# Cap_Piano_Circuit.net
KiCad netlist of a schematic drawn in EAGLE
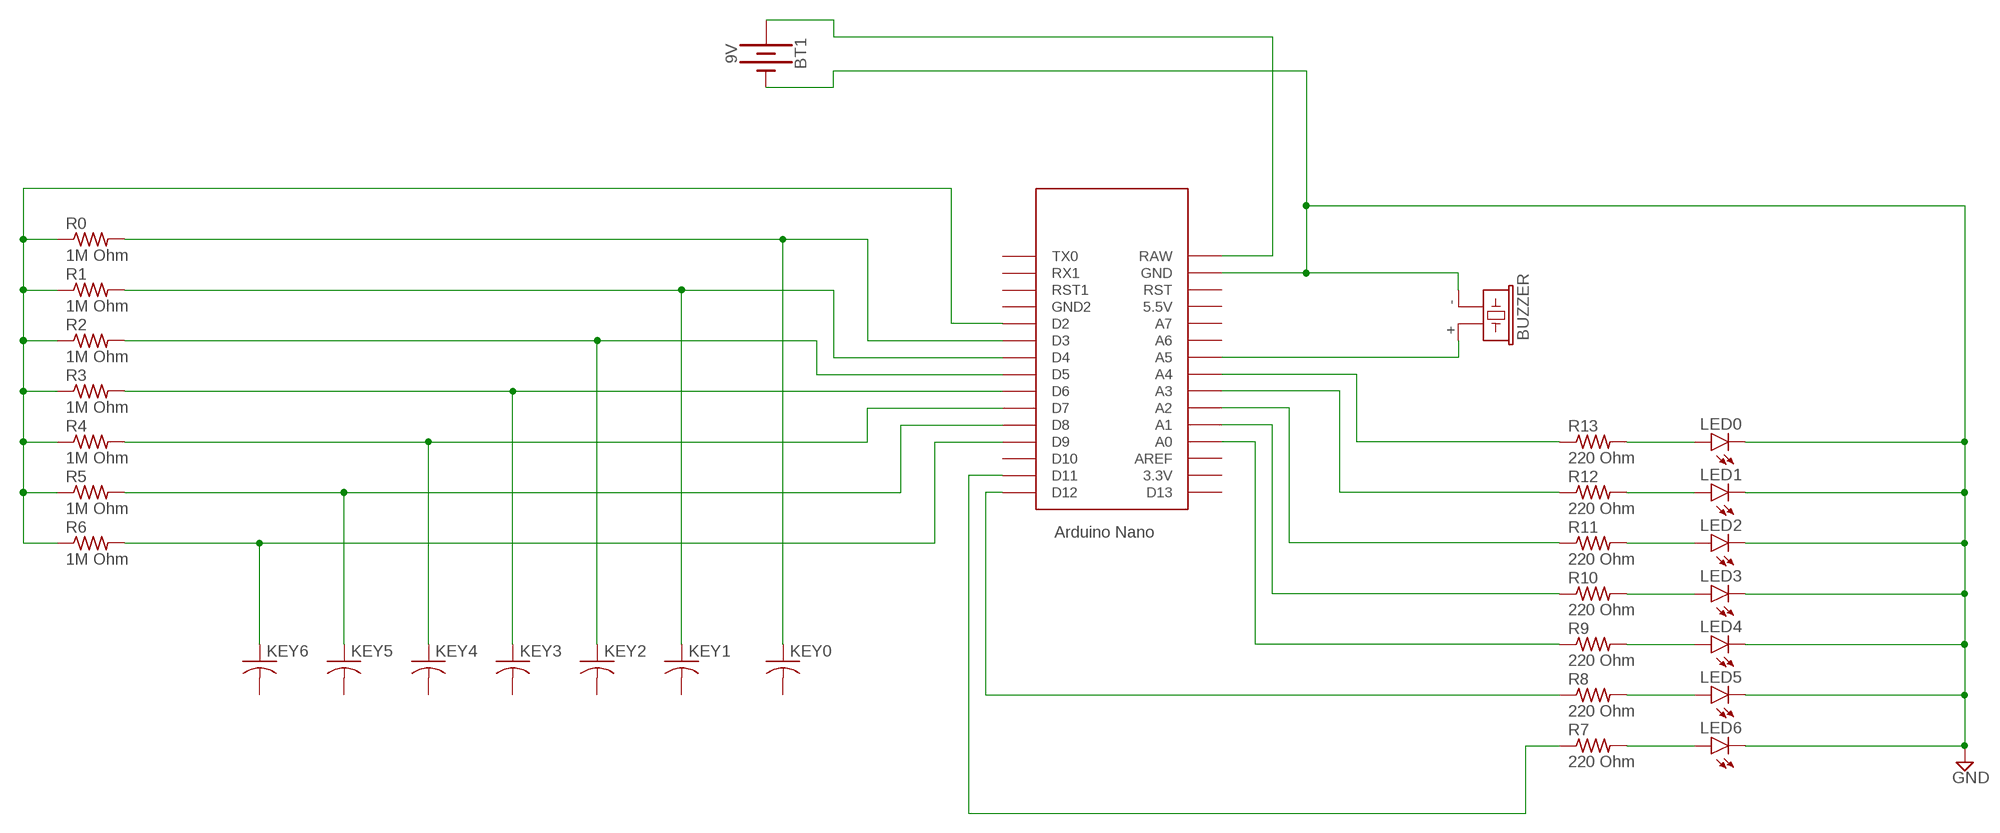
[diagram p0: schematic, sheet 1]

(export (version "E")
  (design (tool "Eeschema 10.0.6"))
  (components
    (comp (ref "BT1")
      (value "9V")
      (footprint "eagle-import:BATTCON_9V")
      (libsource (lib "eagle-import") (part "BATTERY-9V"))
    )
    (comp (ref "BUZZER")
      (value "F/CM12P")
      (footprint "eagle-import:F_CM12P")
      (libsource (lib "eagle-import") (part "F/CM12P"))
    )
    (comp (ref "KEY0")
      (value "C-US050-024X044")
      (footprint "eagle-import:C050-024X044")
      (libsource (lib "eagle-import") (part "C-US050-024X044"))
    )
    (comp (ref "KEY1")
      (value "C-US050-024X044")
      (footprint "eagle-import:C050-024X044")
      (libsource (lib "eagle-import") (part "C-US050-024X044"))
    )
    (comp (ref "KEY2")
      (value "C-US050-024X044")
      (footprint "eagle-import:C050-024X044")
      (libsource (lib "eagle-import") (part "C-US050-024X044"))
    )
    (comp (ref "KEY3")
      (value "C-US050-024X044")
      (footprint "eagle-import:C050-024X044")
      (libsource (lib "eagle-import") (part "C-US050-024X044"))
    )
    (comp (ref "KEY4")
      (value "C-US050-024X044")
      (footprint "eagle-import:C050-024X044")
      (libsource (lib "eagle-import") (part "C-US050-024X044"))
    )
    (comp (ref "KEY5")
      (value "C-US050-024X044")
      (footprint "eagle-import:C050-024X044")
      (libsource (lib "eagle-import") (part "C-US050-024X044"))
    )
    (comp (ref "KEY6")
      (value "C-US050-024X044")
      (footprint "eagle-import:C050-024X044")
      (libsource (lib "eagle-import") (part "C-US050-024X044"))
    )
    (comp (ref "LED0")
      (value "LED5MM")
      (footprint "eagle-import:LED5MM")
      (libsource (lib "eagle-import") (part "LED5MM"))
    )
    (comp (ref "LED1")
      (value "LED5MM")
      (footprint "eagle-import:LED5MM")
      (libsource (lib "eagle-import") (part "LED5MM"))
    )
    (comp (ref "LED2")
      (value "LED5MM")
      (footprint "eagle-import:LED5MM")
      (libsource (lib "eagle-import") (part "LED5MM"))
    )
    (comp (ref "LED3")
      (value "LED5MM")
      (footprint "eagle-import:LED5MM")
      (libsource (lib "eagle-import") (part "LED5MM"))
    )
    (comp (ref "LED4")
      (value "LED5MM")
      (footprint "eagle-import:LED5MM")
      (libsource (lib "eagle-import") (part "LED5MM"))
    )
    (comp (ref "LED5")
      (value "LED5MM")
      (footprint "eagle-import:LED5MM")
      (libsource (lib "eagle-import") (part "LED5MM"))
    )
    (comp (ref "LED6")
      (value "LED5MM")
      (footprint "eagle-import:LED5MM")
      (libsource (lib "eagle-import") (part "LED5MM"))
    )
    (comp (ref "R0")
      (value "1M Ohm")
      (footprint "eagle-import:0204_7")
      (libsource (lib "eagle-import") (part "R-US_0204/7"))
    )
    (comp (ref "R1")
      (value "1M Ohm")
      (footprint "eagle-import:0204_7")
      (libsource (lib "eagle-import") (part "R-US_0204/7"))
    )
    (comp (ref "R2")
      (value "1M Ohm")
      (footprint "eagle-import:0204_7")
      (libsource (lib "eagle-import") (part "R-US_0204/7"))
    )
    (comp (ref "R3")
      (value "1M Ohm")
      (footprint "eagle-import:0204_7")
      (libsource (lib "eagle-import") (part "R-US_0204/7"))
    )
    (comp (ref "R4")
      (value "1M Ohm")
      (footprint "eagle-import:0204_7")
      (libsource (lib "eagle-import") (part "R-US_0204/7"))
    )
    (comp (ref "R5")
      (value "1M Ohm")
      (footprint "eagle-import:0204_7")
      (libsource (lib "eagle-import") (part "R-US_0204/7"))
    )
    (comp (ref "R6")
      (value "1M Ohm")
      (footprint "eagle-import:0204_7")
      (libsource (lib "eagle-import") (part "R-US_0204/7"))
    )
    (comp (ref "R7")
      (value "220 Ohm")
      (footprint "eagle-import:0204_7")
      (libsource (lib "eagle-import") (part "R-US_0204/7"))
    )
    (comp (ref "R8")
      (value "220 Ohm")
      (footprint "eagle-import:0204_7")
      (libsource (lib "eagle-import") (part "R-US_0204/7"))
    )
    (comp (ref "R9")
      (value "220 Ohm")
      (footprint "eagle-import:0204_7")
      (libsource (lib "eagle-import") (part "R-US_0204/7"))
    )
    (comp (ref "R10")
      (value "220 Ohm")
      (footprint "eagle-import:0204_7")
      (libsource (lib "eagle-import") (part "R-US_0204/7"))
    )
    (comp (ref "R11")
      (value "220 Ohm")
      (footprint "eagle-import:0204_7")
      (libsource (lib "eagle-import") (part "R-US_0204/7"))
    )
    (comp (ref "R12")
      (value "220 Ohm")
      (footprint "eagle-import:0204_7")
      (libsource (lib "eagle-import") (part "R-US_0204/7"))
    )
    (comp (ref "R13")
      (value "220 Ohm")
      (footprint "eagle-import:0204_7")
      (libsource (lib "eagle-import") (part "R-US_0204/7"))
    )
    (comp (ref "U$1")
      (value "NANO")
      (footprint "eagle-import:NANO")
      (libsource (lib "eagle-import") (part "NANO"))
    )
  )
  (nets
    (net (code "1") (name "GND") (class "Default")
      (node (ref "BT1") (pin "-") (pinfunction "-_-") (pintype "power_in"))
      (node (ref "BUZZER") (pin "-") (pinfunction "2_-") (pintype "passive"))
      (node (ref "LED0") (pin "K") (pinfunction "C_K") (pintype "passive"))
      (node (ref "LED1") (pin "K") (pinfunction "C_K") (pintype "passive"))
      (node (ref "LED2") (pin "K") (pinfunction "C_K") (pintype "passive"))
      (node (ref "LED3") (pin "K") (pinfunction "C_K") (pintype "passive"))
      (node (ref "LED4") (pin "K") (pinfunction "C_K") (pintype "passive"))
      (node (ref "LED5") (pin "K") (pinfunction "C_K") (pintype "passive"))
      (node (ref "LED6") (pin "K") (pinfunction "C_K") (pintype "passive"))
      (node (ref "U$1") (pin "GND") (pinfunction "GND_GND") (pintype "bidirectional"))
    )
    (net (code "2") (name "Net-(BT1-Pad+)") (class "Default")
      (node (ref "BT1") (pin "+") (pinfunction "+_+") (pintype "power_in"))
      (node (ref "U$1") (pin "RAW") (pinfunction "RAW_RAW") (pintype "bidirectional"))
    )
    (net (code "3") (name "Net-(BUZZER-1)") (class "Default")
      (node (ref "BUZZER") (pin "+") (pinfunction "1_+") (pintype "passive"))
      (node (ref "U$1") (pin "A5") (pinfunction "A5_A5") (pintype "bidirectional"))
    )
    (net (code "4") (name "Net-(KEY0-Pad1)") (class "Default")
      (node (ref "KEY0") (pin "1") (pinfunction "1_1") (pintype "passive"))
      (node (ref "R0") (pin "2") (pinfunction "2_2") (pintype "passive"))
      (node (ref "U$1") (pin "D3") (pinfunction "D3_D3") (pintype "bidirectional"))
    )
    (net (code "5") (name "Net-(KEY1-Pad1)") (class "Default")
      (node (ref "KEY1") (pin "1") (pinfunction "1_1") (pintype "passive"))
      (node (ref "R1") (pin "2") (pinfunction "2_2") (pintype "passive"))
      (node (ref "U$1") (pin "D4") (pinfunction "D4_D4") (pintype "bidirectional"))
    )
    (net (code "6") (name "Net-(KEY2-Pad1)") (class "Default")
      (node (ref "KEY2") (pin "1") (pinfunction "1_1") (pintype "passive"))
      (node (ref "R2") (pin "2") (pinfunction "2_2") (pintype "passive"))
      (node (ref "U$1") (pin "D5") (pinfunction "D5_D5") (pintype "bidirectional"))
    )
    (net (code "7") (name "Net-(KEY3-Pad1)") (class "Default")
      (node (ref "KEY3") (pin "1") (pinfunction "1_1") (pintype "passive"))
      (node (ref "R3") (pin "2") (pinfunction "2_2") (pintype "passive"))
      (node (ref "U$1") (pin "D6") (pinfunction "D6_D6") (pintype "bidirectional"))
    )
    (net (code "8") (name "Net-(KEY4-Pad1)") (class "Default")
      (node (ref "KEY4") (pin "1") (pinfunction "1_1") (pintype "passive"))
      (node (ref "R4") (pin "2") (pinfunction "2_2") (pintype "passive"))
      (node (ref "U$1") (pin "D7") (pinfunction "D7_D7") (pintype "bidirectional"))
    )
    (net (code "9") (name "Net-(KEY5-Pad1)") (class "Default")
      (node (ref "KEY5") (pin "1") (pinfunction "1_1") (pintype "passive"))
      (node (ref "R5") (pin "2") (pinfunction "2_2") (pintype "passive"))
      (node (ref "U$1") (pin "D8") (pinfunction "D8_D8") (pintype "bidirectional"))
    )
    (net (code "10") (name "Net-(KEY6-Pad1)") (class "Default")
      (node (ref "KEY6") (pin "1") (pinfunction "1_1") (pintype "passive"))
      (node (ref "R6") (pin "2") (pinfunction "2_2") (pintype "passive"))
      (node (ref "U$1") (pin "D9") (pinfunction "D9_D9") (pintype "bidirectional"))
    )
    (net (code "11") (name "Net-(LED0-PadA)") (class "Default")
      (node (ref "LED0") (pin "A") (pinfunction "A_A") (pintype "passive"))
      (node (ref "R13") (pin "2") (pinfunction "2_2") (pintype "passive"))
    )
    (net (code "12") (name "Net-(LED1-PadA)") (class "Default")
      (node (ref "LED1") (pin "A") (pinfunction "A_A") (pintype "passive"))
      (node (ref "R12") (pin "2") (pinfunction "2_2") (pintype "passive"))
    )
    (net (code "13") (name "Net-(LED2-PadA)") (class "Default")
      (node (ref "LED2") (pin "A") (pinfunction "A_A") (pintype "passive"))
      (node (ref "R11") (pin "2") (pinfunction "2_2") (pintype "passive"))
    )
    (net (code "14") (name "Net-(LED3-PadA)") (class "Default")
      (node (ref "LED3") (pin "A") (pinfunction "A_A") (pintype "passive"))
      (node (ref "R10") (pin "2") (pinfunction "2_2") (pintype "passive"))
    )
    (net (code "15") (name "Net-(LED4-PadA)") (class "Default")
      (node (ref "LED4") (pin "A") (pinfunction "A_A") (pintype "passive"))
      (node (ref "R9") (pin "2") (pinfunction "2_2") (pintype "passive"))
    )
    (net (code "16") (name "Net-(LED5-PadA)") (class "Default")
      (node (ref "LED5") (pin "A") (pinfunction "A_A") (pintype "passive"))
      (node (ref "R8") (pin "2") (pinfunction "2_2") (pintype "passive"))
    )
    (net (code "17") (name "Net-(LED6-PadA)") (class "Default")
      (node (ref "LED6") (pin "A") (pinfunction "A_A") (pintype "passive"))
      (node (ref "R7") (pin "2") (pinfunction "2_2") (pintype "passive"))
    )
    (net (code "18") (name "Net-(R0-Pad1)") (class "Default")
      (node (ref "R0") (pin "1") (pinfunction "1_1") (pintype "passive"))
      (node (ref "R1") (pin "1") (pinfunction "1_1") (pintype "passive"))
      (node (ref "R2") (pin "1") (pinfunction "1_1") (pintype "passive"))
      (node (ref "R3") (pin "1") (pinfunction "1_1") (pintype "passive"))
      (node (ref "R4") (pin "1") (pinfunction "1_1") (pintype "passive"))
      (node (ref "R5") (pin "1") (pinfunction "1_1") (pintype "passive"))
      (node (ref "R6") (pin "1") (pinfunction "1_1") (pintype "passive"))
      (node (ref "U$1") (pin "D2") (pinfunction "D2_D2") (pintype "bidirectional"))
    )
    (net (code "19") (name "Net-(R7-Pad1)") (class "Default")
      (node (ref "R7") (pin "1") (pinfunction "1_1") (pintype "passive"))
      (node (ref "U$1") (pin "D11") (pinfunction "D11_D11") (pintype "bidirectional"))
    )
    (net (code "20") (name "Net-(R8-Pad1)") (class "Default")
      (node (ref "R8") (pin "1") (pinfunction "1_1") (pintype "passive"))
      (node (ref "U$1") (pin "D12") (pinfunction "D12_D12") (pintype "bidirectional"))
    )
    (net (code "21") (name "Net-(R9-Pad1)") (class "Default")
      (node (ref "R9") (pin "1") (pinfunction "1_1") (pintype "passive"))
      (node (ref "U$1") (pin "A0") (pinfunction "A0_A0") (pintype "bidirectional"))
    )
    (net (code "22") (name "Net-(R10-Pad1)") (class "Default")
      (node (ref "R10") (pin "1") (pinfunction "1_1") (pintype "passive"))
      (node (ref "U$1") (pin "A1") (pinfunction "A1_A1") (pintype "bidirectional"))
    )
    (net (code "23") (name "Net-(R11-Pad1)") (class "Default")
      (node (ref "R11") (pin "1") (pinfunction "1_1") (pintype "passive"))
      (node (ref "U$1") (pin "A2") (pinfunction "A2_A2") (pintype "bidirectional"))
    )
    (net (code "24") (name "Net-(R12-Pad1)") (class "Default")
      (node (ref "R12") (pin "1") (pinfunction "1_1") (pintype "passive"))
      (node (ref "U$1") (pin "A3") (pinfunction "A3_A3") (pintype "bidirectional"))
    )
    (net (code "25") (name "Net-(R13-Pad1)") (class "Default")
      (node (ref "R13") (pin "1") (pinfunction "1_1") (pintype "passive"))
      (node (ref "U$1") (pin "A4") (pinfunction "A4_A4") (pintype "bidirectional"))
    )
    (net (code "26") (name "unconnected-(KEY0-Pad2)") (class "Default")
      (node (ref "KEY0") (pin "2") (pinfunction "2_2") (pintype "passive"))
    )
    (net (code "27") (name "unconnected-(KEY1-Pad2)") (class "Default")
      (node (ref "KEY1") (pin "2") (pinfunction "2_2") (pintype "passive"))
    )
    (net (code "28") (name "unconnected-(KEY2-Pad2)") (class "Default")
      (node (ref "KEY2") (pin "2") (pinfunction "2_2") (pintype "passive"))
    )
    (net (code "29") (name "unconnected-(KEY3-Pad2)") (class "Default")
      (node (ref "KEY3") (pin "2") (pinfunction "2_2") (pintype "passive"))
    )
    (net (code "30") (name "unconnected-(KEY4-Pad2)") (class "Default")
      (node (ref "KEY4") (pin "2") (pinfunction "2_2") (pintype "passive"))
    )
    (net (code "31") (name "unconnected-(KEY5-Pad2)") (class "Default")
      (node (ref "KEY5") (pin "2") (pinfunction "2_2") (pintype "passive"))
    )
    (net (code "32") (name "unconnected-(KEY6-Pad2)") (class "Default")
      (node (ref "KEY6") (pin "2") (pinfunction "2_2") (pintype "passive"))
    )
    (net (code "33") (name "unconnected-(U$1-5.5V-Pad5V)") (class "Default")
      (node (ref "U$1") (pin "5V") (pinfunction "5.5V_5V") (pintype "bidirectional"))
    )
    (net (code "34") (name "unconnected-(U$1-GND2-PadGND1)") (class "Default")
      (node (ref "U$1") (pin "GND1") (pinfunction "GND2_GND1") (pintype "bidirectional"))
    )
    (net (code "35") (name "unconnected-(U$1-Pad3.3V)") (class "Default")
      (node (ref "U$1") (pin "3.3V") (pinfunction "3.3V_3.3V") (pintype "bidirectional"))
    )
    (net (code "36") (name "unconnected-(U$1-PadA6)") (class "Default")
      (node (ref "U$1") (pin "A6") (pinfunction "A6_A6") (pintype "bidirectional"))
    )
    (net (code "37") (name "unconnected-(U$1-PadA7)") (class "Default")
      (node (ref "U$1") (pin "A7") (pinfunction "A7_A7") (pintype "bidirectional"))
    )
    (net (code "38") (name "unconnected-(U$1-PadAREF)") (class "Default")
      (node (ref "U$1") (pin "AREF") (pinfunction "AREF_AREF") (pintype "bidirectional"))
    )
    (net (code "39") (name "unconnected-(U$1-PadD10)") (class "Default")
      (node (ref "U$1") (pin "D10") (pinfunction "D10_D10") (pintype "bidirectional"))
    )
    (net (code "40") (name "unconnected-(U$1-PadD13)") (class "Default")
      (node (ref "U$1") (pin "D13") (pinfunction "D13_D13") (pintype "bidirectional"))
    )
    (net (code "41") (name "unconnected-(U$1-PadICSP1)") (class "Default")
      (node (ref "U$1") (pin "ICSP1") (pinfunction "ICSP1_ICSP1") (pintype "bidirectional"))
    )
    (net (code "42") (name "unconnected-(U$1-PadICSP2)") (class "Default")
      (node (ref "U$1") (pin "ICSP2") (pinfunction "ICSP2_ICSP2") (pintype "bidirectional"))
    )
    (net (code "43") (name "unconnected-(U$1-PadICSP3)") (class "Default")
      (node (ref "U$1") (pin "ICSP3") (pinfunction "ICSP3_ICSP3") (pintype "bidirectional"))
    )
    (net (code "44") (name "unconnected-(U$1-PadICSP4)") (class "Default")
      (node (ref "U$1") (pin "ICSP4") (pinfunction "ICSP4_ICSP4") (pintype "bidirectional"))
    )
    (net (code "45") (name "unconnected-(U$1-PadICSP5)") (class "Default")
      (node (ref "U$1") (pin "ICSP5") (pinfunction "ICSP5_ICSP5") (pintype "bidirectional"))
    )
    (net (code "46") (name "unconnected-(U$1-PadICSP6)") (class "Default")
      (node (ref "U$1") (pin "ICSP6") (pinfunction "ICSP6_ICSP6") (pintype "bidirectional"))
    )
    (net (code "47") (name "unconnected-(U$1-PadRST)") (class "Default")
      (node (ref "U$1") (pin "RST") (pinfunction "RST_RST") (pintype "bidirectional"))
    )
    (net (code "48") (name "unconnected-(U$1-PadRST1)") (class "Default")
      (node (ref "U$1") (pin "RST1") (pinfunction "RST1_RST1") (pintype "bidirectional"))
    )
    (net (code "49") (name "unconnected-(U$1-PadRX1)") (class "Default")
      (node (ref "U$1") (pin "RX1") (pinfunction "RX1_RX1") (pintype "bidirectional"))
    )
    (net (code "50") (name "unconnected-(U$1-PadTX0)") (class "Default")
      (node (ref "U$1") (pin "TX0") (pinfunction "TX0_TX0") (pintype "bidirectional"))
    )
  )
)
